# GBEthernet.net
KiCad netlist of a schematic drawn in Altium Designer
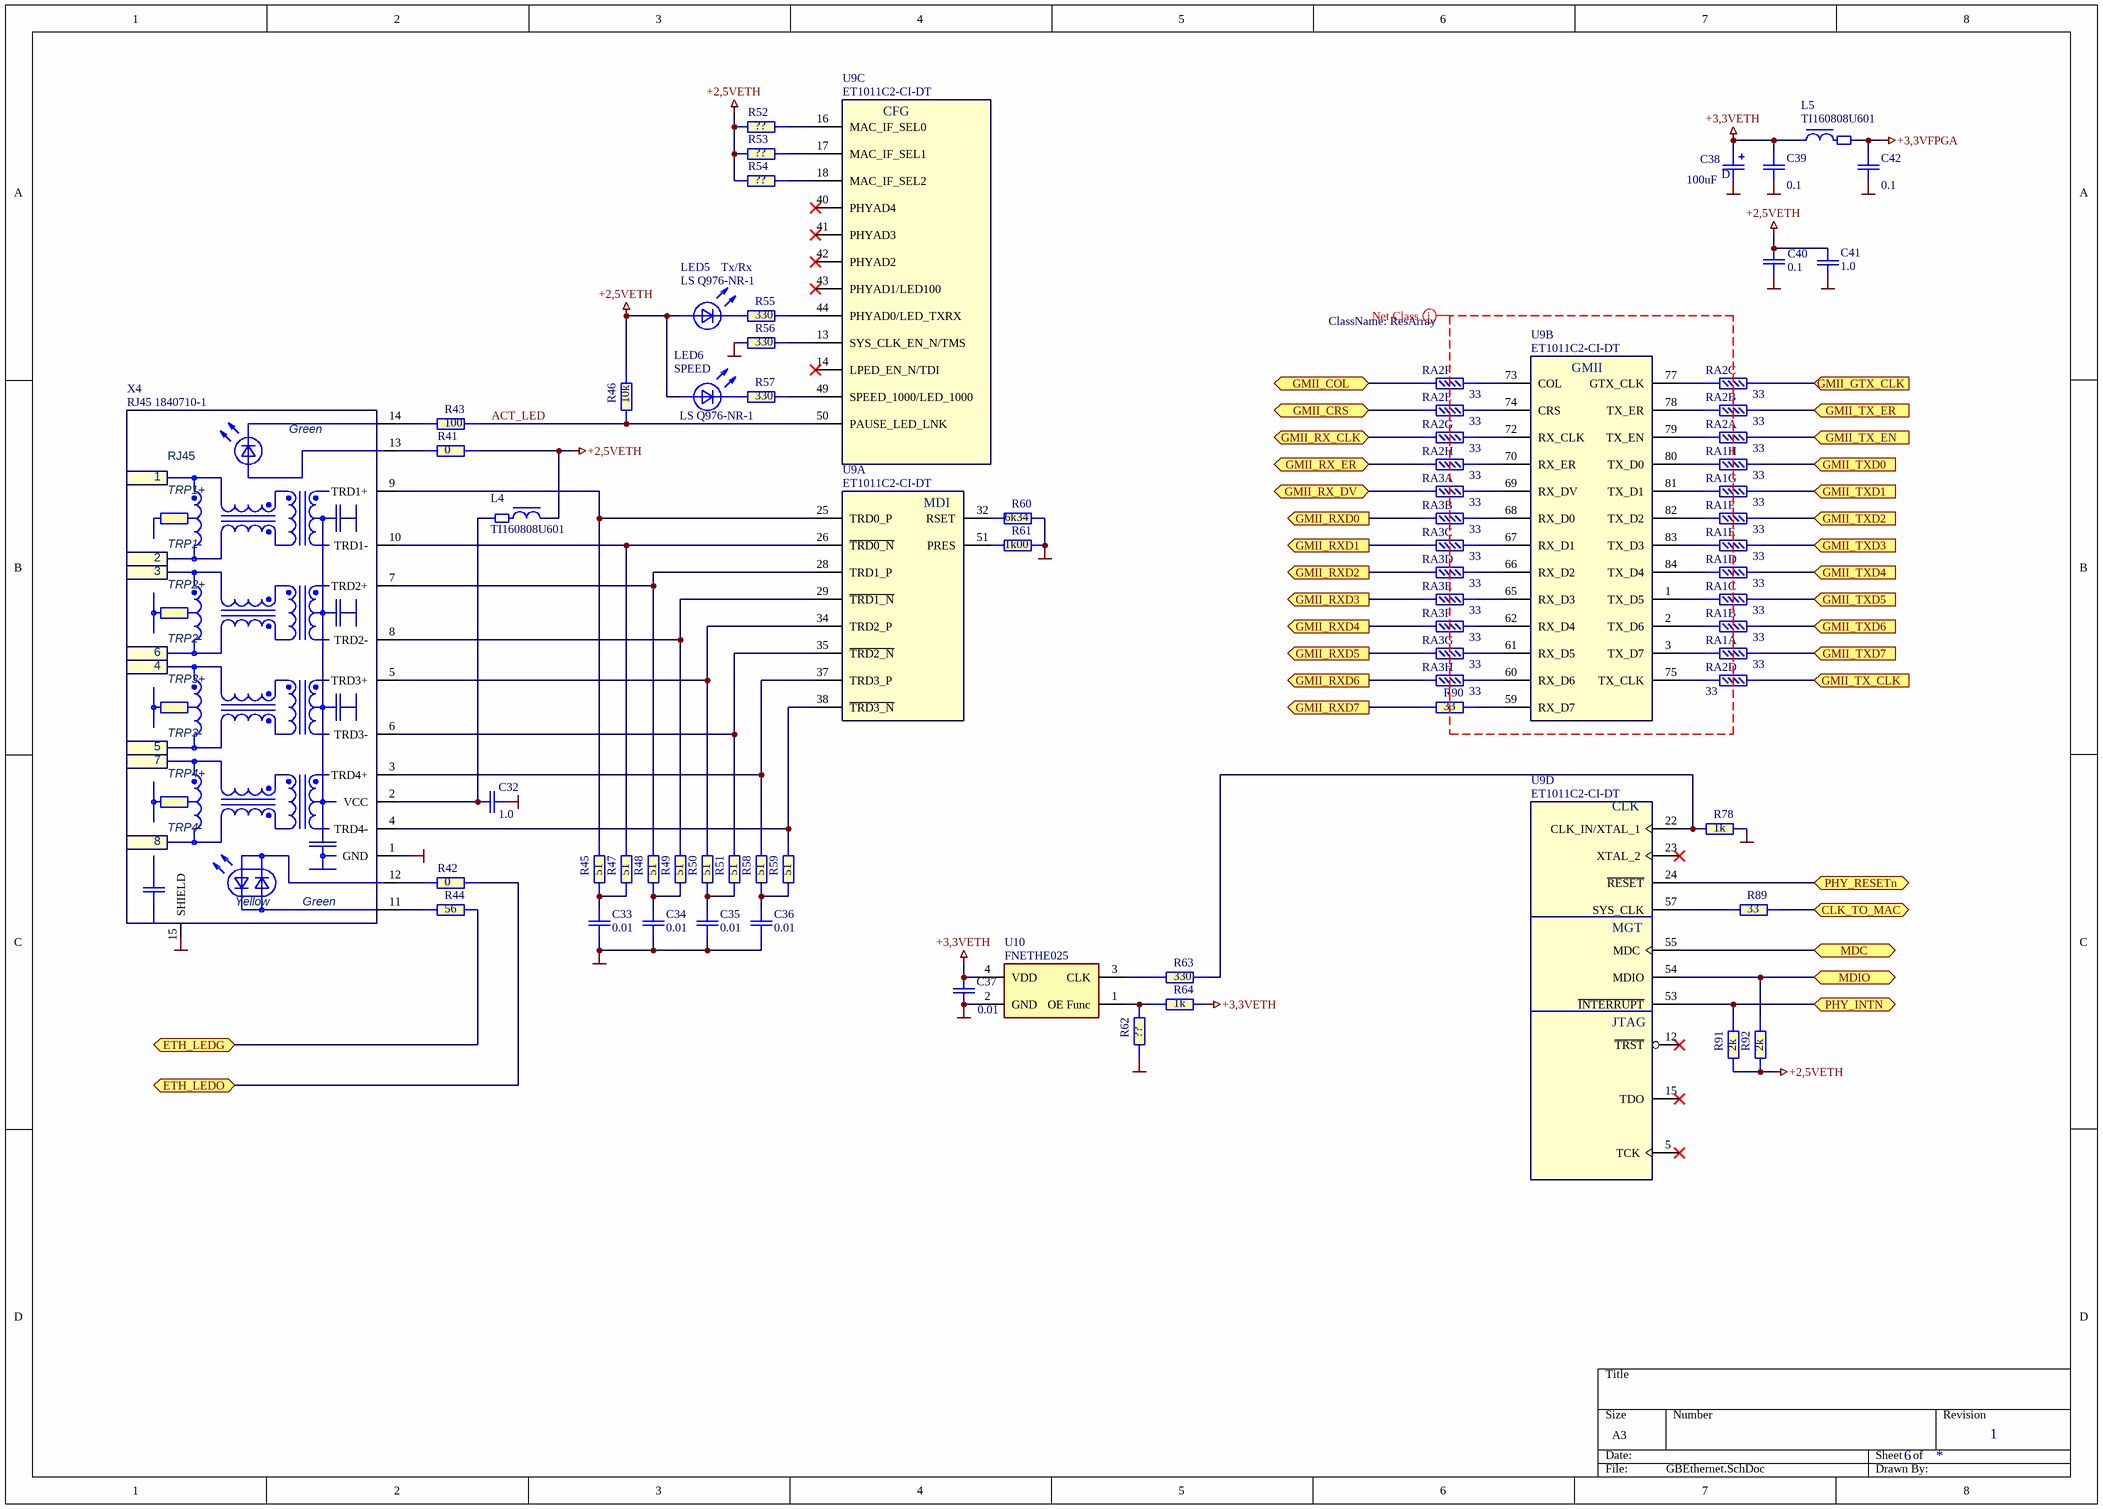
[diagram p0: GBEthernet.SchDoc]

(export (version "E")
  (design (tool "Eeschema 10.0.6"))
  (components
    (comp (ref "C32")
      (value "1.0")
      (footprint "C0603-PHILLIPS")
      (description "Конденсатор")
      (fields (field (name "MANUFACTURER") "MURATA") (field (name "TOLERANCE") "20%"))
      (libsource (lib "Capacitors") (part "C0603"))
    )
    (comp (ref "C33")
      (value "0.01")
      (footprint "C0402-Phillips")
      (description "Конденсатор")
      (fields (field (name "MANUFACTURER") "MURATA") (field (name "TOLERANCE") "20%"))
      (libsource (lib "Capacitors") (part "C0402"))
    )
    (comp (ref "C34")
      (value "0.01")
      (footprint "C0402-Phillips")
      (description "Конденсатор")
      (fields (field (name "MANUFACTURER") "MURATA") (field (name "TOLERANCE") "20%"))
      (libsource (lib "Capacitors") (part "C0402"))
    )
    (comp (ref "C35")
      (value "0.01")
      (footprint "C0402-Phillips")
      (description "Конденсатор")
      (fields (field (name "MANUFACTURER") "MURATA") (field (name "TOLERANCE") "20%"))
      (libsource (lib "Capacitors") (part "C0402"))
    )
    (comp (ref "C36")
      (value "0.01")
      (footprint "C0402-Phillips")
      (description "Конденсатор")
      (fields (field (name "MANUFACTURER") "MURATA") (field (name "TOLERANCE") "20%"))
      (libsource (lib "Capacitors") (part "C0402"))
    )
    (comp (ref "C37")
      (value "0.01")
      (footprint "C0402-Phillips")
      (description "Конденсатор")
      (fields (field (name "MANUFACTURER") "MURATA") (field (name "TOLERANCE") "20%"))
      (libsource (lib "Capacitors") (part "C0402"))
    )
    (comp (ref "C38")
      (value "100uF")
      (footprint "cd7343")
      (description "Конденсатор")
      (fields (field (name "MANUFACTURER") "SPRAGUE"))
      (libsource (lib "Capacitors") (part "CD7343"))
    )
    (comp (ref "C39")
      (value "0.1")
      (footprint "C0402-Phillips")
      (description "Конденсатор")
      (fields (field (name "MANUFACTURER") "MURATA") (field (name "TOLERANCE") "20%"))
      (libsource (lib "Capacitors") (part "C0402"))
    )
    (comp (ref "C40")
      (value "0.1")
      (footprint "C0402-Phillips")
      (description "Конденсатор")
      (fields (field (name "MANUFACTURER") "MURATA") (field (name "TOLERANCE") "20%"))
      (libsource (lib "Capacitors") (part "C0402"))
    )
    (comp (ref "C41")
      (value "1.0")
      (footprint "C0603-PHILLIPS")
      (description "Конденсатор")
      (fields (field (name "MANUFACTURER") "MURATA") (field (name "TOLERANCE") "20%"))
      (libsource (lib "Capacitors") (part "C0603"))
    )
    (comp (ref "C42")
      (value "0.1")
      (footprint "C0402-Phillips")
      (description "Конденсатор")
      (fields (field (name "MANUFACTURER") "MURATA") (field (name "TOLERANCE") "20%"))
      (libsource (lib "Capacitors") (part "C0402"))
    )
    (comp (ref "L4")
      (value "TI160808U601")
      (footprint "Andy:Ti160808-Phillips")
      (description "Дроссель ЭМС")
      (fields (field (name "MANUFACTURER") "MURATA"))
      (libsource (lib "altium-import") (part "root_0_mirrored_TI160808_"))
    )
    (comp (ref "L5")
      (value "TI160808U601")
      (footprint "Andy:Ti160808-Phillips")
      (description "Дроссель ЭМС")
      (fields (field (name "MANUFACTURER") "MURATA"))
      (libsource (lib "altium-import") (part "root_0_TI160808_"))
    )
    (comp (ref "LED5")
      (value "LS Q976-NR-1")
      (footprint "LED-0603y")
      (description "Светодиод")
      (fields (field (name "MANUFACTURER") "OSRAM Opto Semiconductors Inc") (field (name "MISC") "Tx/Rx"))
      (libsource (lib "altium-import") (part "root_1_mirrored_LED0603_"))
    )
    (comp (ref "LED6")
      (value "LS Q976-NR-1")
      (footprint "LED-0603y")
      (description "Светодиод")
      (fields (field (name "MANUFACTURER") "OSRAM Opto Semiconductors Inc") (field (name "MISC") "SPEED"))
      (libsource (lib "altium-import") (part "root_1_mirrored_LED0603_"))
    )
    (comp (ref "R41")
      (value "0")
      (footprint "R0603-PHILLIPS")
      (description "Резистор")
      (fields (field (name "MANUFACTURER") "YAGEO") (field (name "TOLERANCE") "5%"))
      (libsource (lib "altium-import") (part "root_1_R0603_"))
    )
    (comp (ref "R42")
      (value "0")
      (footprint "R0603-PHILLIPS")
      (description "Резистор")
      (fields (field (name "MANUFACTURER") "YAGEO") (field (name "TOLERANCE") "5%"))
      (libsource (lib "altium-import") (part "root_1_R0603_"))
    )
    (comp (ref "R43")
      (value "100")
      (footprint "R0603-PHILLIPS")
      (description "Резистор")
      (fields (field (name "MANUFACTURER") "YAGEO") (field (name "TOLERANCE") "5%"))
      (libsource (lib "altium-import") (part "root_1_R0603_"))
    )
    (comp (ref "R44")
      (value "56")
      (footprint "R0603-PHILLIPS")
      (description "Резистор")
      (fields (field (name "MANUFACTURER") "YAGEO") (field (name "TOLERANCE") "5%"))
      (libsource (lib "altium-import") (part "root_1_R0603_"))
    )
    (comp (ref "R45")
      (value "51")
      (footprint "R0603-PHILLIPS")
      (description "Резистор")
      (fields (field (name "MANUFACTURER") "YAGEO") (field (name "TOLERANCE") "5%"))
      (libsource (lib "altium-import") (part "root_2_R0603_"))
    )
    (comp (ref "R46")
      (value "10k")
      (footprint "R0603-PHILLIPS")
      (description "Резистор")
      (fields (field (name "MANUFACTURER") "YAGEO") (field (name "TOLERANCE") "5%"))
      (libsource (lib "altium-import") (part "root_2_R0603_"))
    )
    (comp (ref "R47")
      (value "51")
      (footprint "R0603-PHILLIPS")
      (description "Резистор")
      (fields (field (name "MANUFACTURER") "YAGEO") (field (name "TOLERANCE") "5%"))
      (libsource (lib "altium-import") (part "root_2_R0603_"))
    )
    (comp (ref "R48")
      (value "51")
      (footprint "R0603-PHILLIPS")
      (description "Резистор")
      (fields (field (name "MANUFACTURER") "YAGEO") (field (name "TOLERANCE") "5%"))
      (libsource (lib "altium-import") (part "root_2_R0603_"))
    )
    (comp (ref "R49")
      (value "51")
      (footprint "R0603-PHILLIPS")
      (description "Резистор")
      (fields (field (name "MANUFACTURER") "YAGEO") (field (name "TOLERANCE") "5%"))
      (libsource (lib "altium-import") (part "root_2_R0603_"))
    )
    (comp (ref "R50")
      (value "51")
      (footprint "R0603-PHILLIPS")
      (description "Резистор")
      (fields (field (name "MANUFACTURER") "YAGEO") (field (name "TOLERANCE") "5%"))
      (libsource (lib "altium-import") (part "root_2_R0603_"))
    )
    (comp (ref "R51")
      (value "51")
      (footprint "R0603-PHILLIPS")
      (description "Резистор")
      (fields (field (name "MANUFACTURER") "YAGEO") (field (name "TOLERANCE") "5%"))
      (libsource (lib "altium-import") (part "root_2_R0603_"))
    )
    (comp (ref "R52")
      (value "??")
      (footprint "R0603-PHILLIPS")
      (description "Резистор")
      (fields (field (name "MANUFACTURER") "YAGEO") (field (name "TOLERANCE") "5%"))
      (libsource (lib "altium-import") (part "root_1_R0603_"))
    )
    (comp (ref "R53")
      (value "??")
      (footprint "R0603-PHILLIPS")
      (description "Резистор")
      (fields (field (name "MANUFACTURER") "YAGEO") (field (name "TOLERANCE") "5%"))
      (libsource (lib "altium-import") (part "root_1_R0603_"))
    )
    (comp (ref "R54")
      (value "??")
      (footprint "R0603-PHILLIPS")
      (description "Резистор")
      (fields (field (name "MANUFACTURER") "YAGEO") (field (name "TOLERANCE") "5%"))
      (libsource (lib "altium-import") (part "root_1_R0603_"))
    )
    (comp (ref "R55")
      (value "330")
      (footprint "R0603-PHILLIPS")
      (description "Резистор")
      (fields (field (name "MANUFACTURER") "YAGEO") (field (name "TOLERANCE") "5%"))
      (libsource (lib "altium-import") (part "root_1_R0603_"))
    )
    (comp (ref "R56")
      (value "330")
      (footprint "R0603-PHILLIPS")
      (description "Резистор")
      (fields (field (name "MANUFACTURER") "YAGEO") (field (name "TOLERANCE") "5%"))
      (libsource (lib "altium-import") (part "root_1_R0603_"))
    )
    (comp (ref "R57")
      (value "330")
      (footprint "R0603-PHILLIPS")
      (description "Резистор")
      (fields (field (name "MANUFACTURER") "YAGEO") (field (name "TOLERANCE") "5%"))
      (libsource (lib "altium-import") (part "root_1_R0603_"))
    )
    (comp (ref "R58")
      (value "51")
      (footprint "R0603-PHILLIPS")
      (description "Резистор")
      (fields (field (name "MANUFACTURER") "YAGEO") (field (name "TOLERANCE") "5%"))
      (libsource (lib "altium-import") (part "root_2_R0603_"))
    )
    (comp (ref "R59")
      (value "51")
      (footprint "R0603-PHILLIPS")
      (description "Резистор")
      (fields (field (name "MANUFACTURER") "YAGEO") (field (name "TOLERANCE") "5%"))
      (libsource (lib "altium-import") (part "root_2_R0603_"))
    )
    (comp (ref "R60")
      (value "6k34")
      (footprint "R0603-PHILLIPS")
      (description "Резистор")
      (fields (field (name "MANUFACTURER") "YAGEO") (field (name "TOLERANCE") "1%"))
      (libsource (lib "altium-import") (part "root_1_R0603_"))
    )
    (comp (ref "R61")
      (value "1k00")
      (footprint "R0603-PHILLIPS")
      (description "Резистор")
      (fields (field (name "MANUFACTURER") "YAGEO") (field (name "TOLERANCE") "1%"))
      (libsource (lib "altium-import") (part "root_1_R0603_"))
    )
    (comp (ref "R62")
      (value "??")
      (footprint "R0603-PHILLIPS")
      (description "Резистор")
      (fields (field (name "MANUFACTURER") "YAGEO") (field (name "TOLERANCE") "5%"))
      (libsource (lib "altium-import") (part "root_2_R0603_"))
    )
    (comp (ref "R63")
      (value "330")
      (footprint "R0603-PHILLIPS")
      (description "Резистор")
      (fields (field (name "MANUFACTURER") "YAGEO") (field (name "TOLERANCE") "5%"))
      (libsource (lib "altium-import") (part "root_1_R0603_"))
    )
    (comp (ref "R64")
      (value "1k")
      (footprint "R0603-PHILLIPS")
      (description "Резистор")
      (fields (field (name "MANUFACTURER") "YAGEO") (field (name "TOLERANCE") "5%"))
      (libsource (lib "altium-import") (part "root_1_R0603_"))
    )
    (comp (ref "R78")
      (value "1k")
      (footprint "R0603-PHILLIPS")
      (description "Резистор")
      (fields (field (name "MANUFACTURER") "YAGEO") (field (name "TOLERANCE") "5%"))
      (libsource (lib "altium-import") (part "root_1_R0603_"))
    )
    (comp (ref "R89")
      (value "33")
      (footprint "R0603-PHILLIPS")
      (description "Резистор")
      (fields (field (name "MANUFACTURER") "YAGEO") (field (name "TOLERANCE") "5%"))
      (libsource (lib "altium-import") (part "root_1_R0603_"))
    )
    (comp (ref "R90")
      (value "33")
      (footprint "R0603-PHILLIPS")
      (description "Резистор")
      (fields (field (name "MANUFACTURER") "YAGEO") (field (name "TOLERANCE") "5%"))
      (libsource (lib "altium-import") (part "root_1_R0603_"))
    )
    (comp (ref "R91")
      (value "2k")
      (footprint "R0603-PHILLIPS")
      (description "Резистор")
      (fields (field (name "MANUFACTURER") "YAGEO") (field (name "TOLERANCE") "5%"))
      (libsource (lib "altium-import") (part "root_2_R0603_"))
    )
    (comp (ref "R92")
      (value "2k")
      (footprint "R0603-PHILLIPS")
      (description "Резистор")
      (fields (field (name "MANUFACTURER") "YAGEO") (field (name "TOLERANCE") "5%"))
      (libsource (lib "altium-import") (part "root_2_R0603_"))
    )
    (comp (ref "RA1")
      (value "33")
      (footprint "YC248")
      (description "Резисторна  сборка")
      (fields (field (name "TOLERANCE") "5%") (field (name "MANUFACTURER") "Yageo"))
      (libsource (lib "") (part "YC248_1"))
    )
    (comp (ref "RA2")
      (value "33")
      (footprint "YC248")
      (description "Резисторна  сборка")
      (fields (field (name "TOLERANCE") "5%") (field (name "MANUFACTURER") "Yageo"))
      (libsource (lib "Resistors") (part "YC248"))
    )
    (comp (ref "RA3")
      (value "33")
      (footprint "YC248")
      (description "Резисторна  сборка")
      (fields (field (name "TOLERANCE") "5%") (field (name "MANUFACTURER") "Yageo"))
      (libsource (lib "Resistors") (part "YC248"))
    )
    (comp (ref "U9")
      (value "ET1011C2-CI-DT")
      (footprint "QFN-84(10x10/0/4mm)with_pad")
      (description "Микросхема")
      (fields (field (name "MANUFACTURER") "LSI"))
      (libsource (lib "altium-import") (part "root_0_ET1011C2-CI-DT_"))
    )
    (comp (ref "U10")
      (value "FNETHE025")
      (footprint "7x5mm")
      (description "Генератор")
      (fields (field (name "MANUFACTURER") "Saronix-eCera"))
      (libsource (lib "altium-import") (part "root_0_mirrored_FNETHE025_"))
    )
    (comp (ref "X4")
      (value "RJ45 1840710-1")
      (footprint "RJ45 1840710-x")
      (description "Модуль разъёма RJ45")
      (fields (field (name "MANUFACTURER") "Tyco Electronics AMP"))
      (libsource (lib "Andy") (part "RJ45 1840710-5"))
    )
  )
  (nets
    (net (code "1") (name "+2,5VETH") (class "Default")
      (node (ref "C40") (pin "1") (pinfunction "1_1") (pintype "passive"))
      (node (ref "C41") (pin "2") (pinfunction "2_2") (pintype "passive"))
      (node (ref "L4") (pin "1") (pinfunction "1_1") (pintype "passive"))
      (node (ref "LED5") (pin "2") (pinfunction "A_2") (pintype "passive"))
      (node (ref "LED6") (pin "2") (pinfunction "A_2") (pintype "passive"))
      (node (ref "R41") (pin "2") (pinfunction "2_2") (pintype "passive"))
      (node (ref "R46") (pin "2") (pinfunction "2_2") (pintype "passive"))
      (node (ref "R52") (pin "1") (pinfunction "1_1") (pintype "passive"))
      (node (ref "R53") (pin "1") (pinfunction "1_1") (pintype "passive"))
      (node (ref "R54") (pin "1") (pinfunction "1_1") (pintype "passive"))
      (node (ref "R91") (pin "1") (pinfunction "1_1") (pintype "passive"))
      (node (ref "R92") (pin "1") (pinfunction "1_1") (pintype "passive"))
    )
    (net (code "2") (name "+3,3VETH") (class "Default")
      (node (ref "C37") (pin "1") (pinfunction "1_1") (pintype "passive"))
      (node (ref "C38") (pin "1") (pinfunction "+_1") (pintype "passive"))
      (node (ref "C39") (pin "1") (pinfunction "1_1") (pintype "passive"))
      (node (ref "L5") (pin "1") (pinfunction "1_1") (pintype "passive"))
      (node (ref "R64") (pin "2") (pinfunction "2_2") (pintype "passive"))
      (node (ref "U10") (pin "4") (pinfunction "VDD_4") (pintype "passive"))
    )
    (net (code "3") (name "+3,3VFPGA") (class "Default")
      (node (ref "C42") (pin "1") (pinfunction "1_1") (pintype "passive"))
      (node (ref "L5") (pin "2") (pinfunction "2_2") (pintype "passive"))
    )
    (net (code "4") (name "/ACT_LED") (class "Default")
      (node (ref "R43") (pin "2") (pinfunction "2_2") (pintype "passive"))
      (node (ref "R46") (pin "1") (pinfunction "1_1") (pintype "passive"))
      (node (ref "U9") (pin "50") (pinfunction "PAUSE_LED_LNK_50") (pintype "passive"))
    )
    (net (code "5") (name "/CLK_TO_MAC") (class "Default")
      (node (ref "R89") (pin "2") (pinfunction "2_2") (pintype "passive"))
    )
    (net (code "6") (name "/ETH_LEDG") (class "Default")
      (node (ref "R44") (pin "2") (pinfunction "2_2") (pintype "passive"))
    )
    (net (code "7") (name "/ETH_LEDO") (class "Default")
      (node (ref "R42") (pin "2") (pinfunction "2_2") (pintype "passive"))
    )
    (net (code "8") (name "/GMII_COL") (class "Default")
      (node (ref "RA2") (pin "11") (pinfunction "2_11") (pintype "passive"))
    )
    (net (code "9") (name "/GMII_CRS") (class "Default")
      (node (ref "RA2") (pin "12") (pinfunction "2_12") (pintype "passive"))
    )
    (net (code "10") (name "/GMII_GTX_CLK") (class "Default")
      (node (ref "RA2") (pin "14") (pinfunction "2_14") (pintype "passive"))
    )
    (net (code "11") (name "/GMII_RXD0") (class "Default")
      (node (ref "RA3") (pin "15") (pinfunction "2_15") (pintype "passive"))
    )
    (net (code "12") (name "/GMII_RXD1") (class "Default")
      (node (ref "RA3") (pin "14") (pinfunction "2_14") (pintype "passive"))
    )
    (net (code "13") (name "/GMII_RXD2") (class "Default")
      (node (ref "RA3") (pin "13") (pinfunction "2_13") (pintype "passive"))
    )
    (net (code "14") (name "/GMII_RXD3") (class "Default")
      (node (ref "RA3") (pin "12") (pinfunction "2_12") (pintype "passive"))
    )
    (net (code "15") (name "/GMII_RXD4") (class "Default")
      (node (ref "RA3") (pin "11") (pinfunction "2_11") (pintype "passive"))
    )
    (net (code "16") (name "/GMII_RXD5") (class "Default")
      (node (ref "RA3") (pin "10") (pinfunction "2_10") (pintype "passive"))
    )
    (net (code "17") (name "/GMII_RXD6") (class "Default")
      (node (ref "RA3") (pin "9") (pinfunction "2_9") (pintype "passive"))
    )
    (net (code "18") (name "/GMII_RXD7") (class "Default")
      (node (ref "R90") (pin "1") (pinfunction "1_1") (pintype "passive"))
    )
    (net (code "19") (name "/GMII_RX_CLK") (class "Default")
      (node (ref "RA2") (pin "10") (pinfunction "2_10") (pintype "passive"))
    )
    (net (code "20") (name "/GMII_RX_DV") (class "Default")
      (node (ref "RA3") (pin "16") (pinfunction "2_16") (pintype "passive"))
    )
    (net (code "21") (name "/GMII_RX_ER") (class "Default")
      (node (ref "RA2") (pin "9") (pinfunction "2_9") (pintype "passive"))
    )
    (net (code "22") (name "/GMII_TXD0") (class "Default")
      (node (ref "RA1") (pin "9") (pinfunction "2_9") (pintype "passive"))
    )
    (net (code "23") (name "/GMII_TXD1") (class "Default")
      (node (ref "RA1") (pin "10") (pinfunction "2_10") (pintype "passive"))
    )
    (net (code "24") (name "/GMII_TXD2") (class "Default")
      (node (ref "RA1") (pin "11") (pinfunction "2_11") (pintype "passive"))
    )
    (net (code "25") (name "/GMII_TXD3") (class "Default")
      (node (ref "RA1") (pin "12") (pinfunction "2_12") (pintype "passive"))
    )
    (net (code "26") (name "/GMII_TXD4") (class "Default")
      (node (ref "RA1") (pin "13") (pinfunction "2_13") (pintype "passive"))
    )
    (net (code "27") (name "/GMII_TXD5") (class "Default")
      (node (ref "RA1") (pin "14") (pinfunction "2_14") (pintype "passive"))
    )
    (net (code "28") (name "/GMII_TXD6") (class "Default")
      (node (ref "RA1") (pin "15") (pinfunction "2_15") (pintype "passive"))
    )
    (net (code "29") (name "/GMII_TXD7") (class "Default")
      (node (ref "RA1") (pin "16") (pinfunction "2_16") (pintype "passive"))
    )
    (net (code "30") (name "/GMII_TX_CLK") (class "Default")
      (node (ref "RA2") (pin "13") (pinfunction "2_13") (pintype "passive"))
    )
    (net (code "31") (name "/GMII_TX_EN") (class "Default")
      (node (ref "RA2") (pin "16") (pinfunction "2_16") (pintype "passive"))
    )
    (net (code "32") (name "/GMII_TX_ER") (class "Default")
      (node (ref "RA2") (pin "15") (pinfunction "2_15") (pintype "passive"))
    )
    (net (code "33") (name "/MDC") (class "Default")
      (node (ref "U9") (pin "55") (pinfunction "MDC_55") (pintype "passive"))
    )
    (net (code "34") (name "/MDIO") (class "Default")
      (node (ref "R92") (pin "2") (pinfunction "2_2") (pintype "passive"))
      (node (ref "U9") (pin "54") (pinfunction "MDIO_54") (pintype "passive"))
    )
    (net (code "35") (name "/PHY_INTN") (class "Default")
      (node (ref "R91") (pin "2") (pinfunction "2_2") (pintype "passive"))
      (node (ref "U9") (pin "53") (pinfunction "~{INTERRUPT}_53") (pintype "passive"))
    )
    (net (code "36") (name "/PHY_RESETn") (class "Default")
      (node (ref "U9") (pin "24") (pinfunction "~{RESET}_24") (pintype "passive"))
    )
    (net (code "37") (name "GND") (class "Default")
      (node (ref "C32") (pin "1") (pinfunction "1_1") (pintype "passive"))
      (node (ref "C33") (pin "2") (pinfunction "2_2") (pintype "passive"))
      (node (ref "C34") (pin "2") (pinfunction "2_2") (pintype "passive"))
      (node (ref "C35") (pin "2") (pinfunction "2_2") (pintype "passive"))
      (node (ref "C36") (pin "2") (pinfunction "2_2") (pintype "passive"))
      (node (ref "C37") (pin "2") (pinfunction "2_2") (pintype "passive"))
      (node (ref "C38") (pin "2") (pinfunction "-_2") (pintype "passive"))
      (node (ref "C39") (pin "2") (pinfunction "2_2") (pintype "passive"))
      (node (ref "C40") (pin "2") (pinfunction "2_2") (pintype "passive"))
      (node (ref "C41") (pin "1") (pinfunction "1_1") (pintype "passive"))
      (node (ref "C42") (pin "2") (pinfunction "2_2") (pintype "passive"))
      (node (ref "R56") (pin "1") (pinfunction "1_1") (pintype "passive"))
      (node (ref "R60") (pin "2") (pinfunction "2_2") (pintype "passive"))
      (node (ref "R61") (pin "2") (pinfunction "2_2") (pintype "passive"))
      (node (ref "R62") (pin "1") (pinfunction "1_1") (pintype "passive"))
      (node (ref "R78") (pin "2") (pinfunction "2_2") (pintype "passive"))
      (node (ref "U10") (pin "2") (pinfunction "GND_2") (pintype "passive"))
      (node (ref "X4") (pin "1") (pinfunction "GND_1") (pintype "passive"))
      (node (ref "X4") (pin "15") (pinfunction "SHIELD_15") (pintype "passive"))
    )
    (net (code "38") (name "Net-(C33-Pad1)") (class "Default")
      (node (ref "C33") (pin "1") (pinfunction "1_1") (pintype "passive"))
      (node (ref "R45") (pin "1") (pinfunction "1_1") (pintype "passive"))
      (node (ref "R47") (pin "1") (pinfunction "1_1") (pintype "passive"))
    )
    (net (code "39") (name "Net-(C34-Pad1)") (class "Default")
      (node (ref "C34") (pin "1") (pinfunction "1_1") (pintype "passive"))
      (node (ref "R48") (pin "1") (pinfunction "1_1") (pintype "passive"))
      (node (ref "R49") (pin "1") (pinfunction "1_1") (pintype "passive"))
    )
    (net (code "40") (name "Net-(C35-Pad1)") (class "Default")
      (node (ref "C35") (pin "1") (pinfunction "1_1") (pintype "passive"))
      (node (ref "R50") (pin "1") (pinfunction "1_1") (pintype "passive"))
      (node (ref "R51") (pin "1") (pinfunction "1_1") (pintype "passive"))
    )
    (net (code "41") (name "Net-(C36-Pad1)") (class "Default")
      (node (ref "C36") (pin "1") (pinfunction "1_1") (pintype "passive"))
      (node (ref "R58") (pin "1") (pinfunction "1_1") (pintype "passive"))
      (node (ref "R59") (pin "1") (pinfunction "1_1") (pintype "passive"))
    )
    (net (code "42") (name "Net-(LED5-K)") (class "Default")
      (node (ref "LED5") (pin "1") (pinfunction "K_1") (pintype "passive"))
      (node (ref "R55") (pin "1") (pinfunction "1_1") (pintype "passive"))
    )
    (net (code "43") (name "Net-(LED6-K)") (class "Default")
      (node (ref "LED6") (pin "1") (pinfunction "K_1") (pintype "passive"))
      (node (ref "R57") (pin "1") (pinfunction "1_1") (pintype "passive"))
    )
    (net (code "44") (name "Net-(RA1B-1)") (class "Default")
      (node (ref "RA1") (pin "2") (pinfunction "1_2") (pintype "passive"))
      (node (ref "U9") (pin "2") (pinfunction "TX_D6_2") (pintype "passive"))
    )
    (net (code "45") (name "Net-(RA1C-1)") (class "Default")
      (node (ref "RA1") (pin "3") (pinfunction "1_3") (pintype "passive"))
      (node (ref "U9") (pin "1") (pinfunction "TX_D5_1") (pintype "passive"))
    )
    (net (code "46") (name "Net-(RA1D-1)") (class "Default")
      (node (ref "RA1") (pin "4") (pinfunction "1_4") (pintype "passive"))
      (node (ref "U9") (pin "84") (pinfunction "TX_D4_84") (pintype "passive"))
    )
    (net (code "47") (name "Net-(RA1E-1)") (class "Default")
      (node (ref "RA1") (pin "5") (pinfunction "1_5") (pintype "passive"))
      (node (ref "U9") (pin "83") (pinfunction "TX_D3_83") (pintype "passive"))
    )
    (net (code "48") (name "Net-(RA1F-1)") (class "Default")
      (node (ref "RA1") (pin "6") (pinfunction "1_6") (pintype "passive"))
      (node (ref "U9") (pin "82") (pinfunction "TX_D2_82") (pintype "passive"))
    )
    (net (code "49") (name "Net-(RA1G-1)") (class "Default")
      (node (ref "RA1") (pin "7") (pinfunction "1_7") (pintype "passive"))
      (node (ref "U9") (pin "81") (pinfunction "TX_D1_81") (pintype "passive"))
    )
    (net (code "50") (name "Net-(RA1H-1)") (class "Default")
      (node (ref "RA1") (pin "8") (pinfunction "1_8") (pintype "passive"))
      (node (ref "U9") (pin "80") (pinfunction "TX_D0_80") (pintype "passive"))
    )
    (net (code "51") (name "Net-(RA2B-1)") (class "Default")
      (node (ref "RA2") (pin "2") (pinfunction "1_2") (pintype "passive"))
      (node (ref "U9") (pin "78") (pinfunction "TX_ER_78") (pintype "passive"))
    )
    (net (code "52") (name "Net-(RA2C-1)") (class "Default")
      (node (ref "RA2") (pin "3") (pinfunction "1_3") (pintype "passive"))
      (node (ref "U9") (pin "77") (pinfunction "GTX_CLK_77") (pintype "passive"))
    )
    (net (code "53") (name "Net-(RA2D-1)") (class "Default")
      (node (ref "RA2") (pin "4") (pinfunction "1_4") (pintype "passive"))
      (node (ref "U9") (pin "75") (pinfunction "TX_CLK_75") (pintype "passive"))
    )
    (net (code "54") (name "Net-(RA2E-1)") (class "Default")
      (node (ref "RA2") (pin "5") (pinfunction "1_5") (pintype "passive"))
      (node (ref "U9") (pin "74") (pinfunction "CRS_74") (pintype "passive"))
    )
    (net (code "55") (name "Net-(RA2F-1)") (class "Default")
      (node (ref "RA2") (pin "6") (pinfunction "1_6") (pintype "passive"))
      (node (ref "U9") (pin "73") (pinfunction "COL_73") (pintype "passive"))
    )
    (net (code "56") (name "Net-(RA2G-1)") (class "Default")
      (node (ref "RA2") (pin "7") (pinfunction "1_7") (pintype "passive"))
      (node (ref "U9") (pin "72") (pinfunction "RX_CLK_72") (pintype "passive"))
    )
    (net (code "57") (name "Net-(RA2H-1)") (class "Default")
      (node (ref "RA2") (pin "8") (pinfunction "1_8") (pintype "passive"))
      (node (ref "U9") (pin "70") (pinfunction "RX_ER_70") (pintype "passive"))
    )
    (net (code "58") (name "Net-(RA3B-1)") (class "Default")
      (node (ref "RA3") (pin "2") (pinfunction "1_2") (pintype "passive"))
      (node (ref "U9") (pin "68") (pinfunction "RX_D0_68") (pintype "passive"))
    )
    (net (code "59") (name "Net-(RA3C-1)") (class "Default")
      (node (ref "RA3") (pin "3") (pinfunction "1_3") (pintype "passive"))
      (node (ref "U9") (pin "67") (pinfunction "RX_D1_67") (pintype "passive"))
    )
    (net (code "60") (name "Net-(RA3D-1)") (class "Default")
      (node (ref "RA3") (pin "4") (pinfunction "1_4") (pintype "passive"))
      (node (ref "U9") (pin "66") (pinfunction "RX_D2_66") (pintype "passive"))
    )
    (net (code "61") (name "Net-(RA3E-1)") (class "Default")
      (node (ref "RA3") (pin "5") (pinfunction "1_5") (pintype "passive"))
      (node (ref "U9") (pin "65") (pinfunction "RX_D3_65") (pintype "passive"))
    )
    (net (code "62") (name "Net-(RA3F-1)") (class "Default")
      (node (ref "RA3") (pin "6") (pinfunction "1_6") (pintype "passive"))
      (node (ref "U9") (pin "62") (pinfunction "RX_D4_62") (pintype "passive"))
    )
    (net (code "63") (name "Net-(RA3G-1)") (class "Default")
      (node (ref "RA3") (pin "7") (pinfunction "1_7") (pintype "passive"))
      (node (ref "U9") (pin "61") (pinfunction "RX_D5_61") (pintype "passive"))
    )
    (net (code "64") (name "Net-(RA3H-1)") (class "Default")
      (node (ref "RA3") (pin "8") (pinfunction "1_8") (pintype "passive"))
      (node (ref "U9") (pin "60") (pinfunction "RX_D6_60") (pintype "passive"))
    )
    (net (code "65") (name "Net-(U9A-PRES)") (class "Default")
      (node (ref "R61") (pin "1") (pinfunction "1_1") (pintype "passive"))
      (node (ref "U9") (pin "51") (pinfunction "PRES_51") (pintype "passive"))
    )
    (net (code "66") (name "Net-(U9A-RSET)") (class "Default")
      (node (ref "R60") (pin "1") (pinfunction "1_1") (pintype "passive"))
      (node (ref "U9") (pin "32") (pinfunction "RSET_32") (pintype "passive"))
    )
    (net (code "67") (name "Net-(U9A-TRD0_P)") (class "Default")
      (node (ref "R45") (pin "2") (pinfunction "2_2") (pintype "passive"))
      (node (ref "U9") (pin "25") (pinfunction "TRD0_P_25") (pintype "passive"))
      (node (ref "X4") (pin "9") (pinfunction "TRD1+_9") (pintype "passive"))
    )
    (net (code "68") (name "Net-(U9A-TRD1_P)") (class "Default")
      (node (ref "R48") (pin "2") (pinfunction "2_2") (pintype "passive"))
      (node (ref "U9") (pin "28") (pinfunction "TRD1_P_28") (pintype "passive"))
      (node (ref "X4") (pin "7") (pinfunction "TRD2+_7") (pintype "passive"))
    )
    (net (code "69") (name "Net-(U9A-TRD2_P)") (class "Default")
      (node (ref "R50") (pin "2") (pinfunction "2_2") (pintype "passive"))
      (node (ref "U9") (pin "34") (pinfunction "TRD2_P_34") (pintype "passive"))
      (node (ref "X4") (pin "5") (pinfunction "TRD3+_5") (pintype "passive"))
    )
    (net (code "70") (name "Net-(U9A-TRD3_P)") (class "Default")
      (node (ref "R58") (pin "2") (pinfunction "2_2") (pintype "passive"))
      (node (ref "U9") (pin "37") (pinfunction "TRD3_P_37") (pintype "passive"))
      (node (ref "X4") (pin "3") (pinfunction "TRD4+_3") (pintype "passive"))
    )
    (net (code "71") (name "Net-(U9A-~{TRD0_N})") (class "Default")
      (node (ref "R47") (pin "2") (pinfunction "2_2") (pintype "passive"))
      (node (ref "U9") (pin "26") (pinfunction "~{TRD0_N}_26") (pintype "passive"))
      (node (ref "X4") (pin "10") (pinfunction "TRD1-_10") (pintype "passive"))
    )
    (net (code "72") (name "Net-(U9A-~{TRD1_N})") (class "Default")
      (node (ref "R49") (pin "2") (pinfunction "2_2") (pintype "passive"))
      (node (ref "U9") (pin "29") (pinfunction "~{TRD1_N}_29") (pintype "passive"))
      (node (ref "X4") (pin "8") (pinfunction "TRD2-_8") (pintype "passive"))
    )
    (net (code "73") (name "Net-(U9A-~{TRD2_N})") (class "Default")
      (node (ref "R51") (pin "2") (pinfunction "2_2") (pintype "passive"))
      (node (ref "U9") (pin "35") (pinfunction "~{TRD2_N}_35") (pintype "passive"))
      (node (ref "X4") (pin "6") (pinfunction "TRD3-_6") (pintype "passive"))
    )
    (net (code "74") (name "Net-(U9A-~{TRD3_N})") (class "Default")
      (node (ref "R59") (pin "2") (pinfunction "2_2") (pintype "passive"))
      (node (ref "U9") (pin "38") (pinfunction "~{TRD3_N}_38") (pintype "passive"))
      (node (ref "X4") (pin "4") (pinfunction "TRD4-_4") (pintype "passive"))
    )
    (net (code "75") (name "Net-(U9B-RX_D7)") (class "Default")
      (node (ref "R90") (pin "2") (pinfunction "2_2") (pintype "passive"))
      (node (ref "U9") (pin "59") (pinfunction "RX_D7_59") (pintype "passive"))
    )
    (net (code "76") (name "Net-(U9B-RX_DV)") (class "Default")
      (node (ref "RA3") (pin "1") (pinfunction "1_1") (pintype "passive"))
      (node (ref "U9") (pin "69") (pinfunction "RX_DV_69") (pintype "passive"))
    )
    (net (code "77") (name "Net-(U9B-TX_D7)") (class "Default")
      (node (ref "RA1") (pin "1") (pinfunction "1_1") (pintype "passive"))
      (node (ref "U9") (pin "3") (pinfunction "TX_D7_3") (pintype "passive"))
    )
    (net (code "78") (name "Net-(U9B-TX_EN)") (class "Default")
      (node (ref "RA2") (pin "1") (pinfunction "1_1") (pintype "passive"))
      (node (ref "U9") (pin "79") (pinfunction "TX_EN_79") (pintype "passive"))
    )
    (net (code "79") (name "Net-(U9C-MAC_IF_SEL0)") (class "Default")
      (node (ref "R52") (pin "2") (pinfunction "2_2") (pintype "passive"))
      (node (ref "U9") (pin "16") (pinfunction "MAC_IF_SEL0_16") (pintype "passive"))
    )
    (net (code "80") (name "Net-(U9C-MAC_IF_SEL1)") (class "Default")
      (node (ref "R53") (pin "2") (pinfunction "2_2") (pintype "passive"))
      (node (ref "U9") (pin "17") (pinfunction "MAC_IF_SEL1_17") (pintype "passive"))
    )
    (net (code "81") (name "Net-(U9C-MAC_IF_SEL2)") (class "Default")
      (node (ref "R54") (pin "2") (pinfunction "2_2") (pintype "passive"))
      (node (ref "U9") (pin "18") (pinfunction "MAC_IF_SEL2_18") (pintype "passive"))
    )
    (net (code "82") (name "Net-(U9C-PHYAD0{slash}LED_TXRX)") (class "Default")
      (node (ref "R55") (pin "2") (pinfunction "2_2") (pintype "passive"))
      (node (ref "U9") (pin "44") (pinfunction "PHYAD0/LED_TXRX_44") (pintype "passive"))
    )
    (net (code "83") (name "Net-(U9C-SPEED_1000{slash}LED_1000)") (class "Default")
      (node (ref "R57") (pin "2") (pinfunction "2_2") (pintype "passive"))
      (node (ref "U9") (pin "49") (pinfunction "SPEED_1000/LED_1000_49") (pintype "passive"))
    )
    (net (code "84") (name "Net-(U9C-SYS_CLK_EN_N{slash}TMS)") (class "Default")
      (node (ref "R56") (pin "2") (pinfunction "2_2") (pintype "passive"))
      (node (ref "U9") (pin "13") (pinfunction "SYS_CLK_EN_N/TMS_13") (pintype "passive"))
    )
    (net (code "85") (name "Net-(U9D-CLK_IN{slash}XTAL_1)") (class "Default")
      (node (ref "R63") (pin "2") (pinfunction "2_2") (pintype "passive"))
      (node (ref "R78") (pin "1") (pinfunction "1_1") (pintype "passive"))
      (node (ref "U9") (pin "22") (pinfunction "CLK_IN/XTAL_1_22") (pintype "passive"))
    )
    (net (code "86") (name "Net-(U9D-SYS_CLK)") (class "Default")
      (node (ref "R89") (pin "1") (pinfunction "1_1") (pintype "passive"))
      (node (ref "U9") (pin "57") (pinfunction "SYS_CLK_57") (pintype "passive"))
    )
    (net (code "87") (name "Net-(U10-CLK)") (class "Default")
      (node (ref "R63") (pin "1") (pinfunction "1_1") (pintype "passive"))
      (node (ref "U10") (pin "3") (pinfunction "CLK_3") (pintype "passive"))
    )
    (net (code "88") (name "Net-(U10-OE_Func)") (class "Default")
      (node (ref "R62") (pin "2") (pinfunction "2_2") (pintype "passive"))
      (node (ref "R64") (pin "1") (pinfunction "1_1") (pintype "passive"))
      (node (ref "U10") (pin "1") (pinfunction "OE_Func_1") (pintype "passive"))
    )
    (net (code "89") (name "Net-(X4-LED1+)") (class "Default")
      (node (ref "R41") (pin "1") (pinfunction "1_1") (pintype "passive"))
      (node (ref "X4") (pin "13") (pinfunction "LED1+_13") (pintype "passive"))
    )
    (net (code "90") (name "Net-(X4-LED1-)") (class "Default")
      (node (ref "R43") (pin "1") (pinfunction "1_1") (pintype "passive"))
      (node (ref "X4") (pin "14") (pinfunction "LED1-_14") (pintype "passive"))
    )
    (net (code "91") (name "Net-(X4-LED2+G)") (class "Default")
      (node (ref "R44") (pin "1") (pinfunction "1_1") (pintype "passive"))
      (node (ref "X4") (pin "11") (pinfunction "LED2+G_11") (pintype "passive"))
    )
    (net (code "92") (name "Net-(X4-LED2+Y)") (class "Default")
      (node (ref "R42") (pin "1") (pinfunction "1_1") (pintype "passive"))
      (node (ref "X4") (pin "12") (pinfunction "LED2+Y_12") (pintype "passive"))
    )
    (net (code "93") (name "Net-(X4-VCC)") (class "Default")
      (node (ref "C32") (pin "2") (pinfunction "2_2") (pintype "passive"))
      (node (ref "L4") (pin "2") (pinfunction "2_2") (pintype "passive"))
      (node (ref "X4") (pin "2") (pinfunction "VCC_2") (pintype "passive"))
    )
    (net (code "94") (name "unconnected-(U9C-LPED_EN_N{slash}TDI-Pad14)") (class "Default")
      (node (ref "U9") (pin "14") (pinfunction "LPED_EN_N/TDI_14") (pintype "passive+no_connect"))
    )
    (net (code "95") (name "unconnected-(U9C-PHYAD1{slash}LED100-Pad43)") (class "Default")
      (node (ref "U9") (pin "43") (pinfunction "PHYAD1/LED100_43") (pintype "passive+no_connect"))
    )
    (net (code "96") (name "unconnected-(U9C-PHYAD2-Pad42)") (class "Default")
      (node (ref "U9") (pin "42") (pinfunction "PHYAD2_42") (pintype "passive+no_connect"))
    )
    (net (code "97") (name "unconnected-(U9C-PHYAD3-Pad41)") (class "Default")
      (node (ref "U9") (pin "41") (pinfunction "PHYAD3_41") (pintype "passive+no_connect"))
    )
    (net (code "98") (name "unconnected-(U9C-PHYAD4-Pad40)") (class "Default")
      (node (ref "U9") (pin "40") (pinfunction "PHYAD4_40") (pintype "passive+no_connect"))
    )
    (net (code "99") (name "unconnected-(U9D-TCK-Pad5)") (class "Default")
      (node (ref "U9") (pin "5") (pinfunction "TCK_5") (pintype "passive+no_connect"))
    )
    (net (code "100") (name "unconnected-(U9D-TDO-Pad15)") (class "Default")
      (node (ref "U9") (pin "15") (pinfunction "TDO_15") (pintype "passive+no_connect"))
    )
    (net (code "101") (name "unconnected-(U9D-XTAL_2-Pad23)") (class "Default")
      (node (ref "U9") (pin "23") (pinfunction "XTAL_2_23") (pintype "passive+no_connect"))
    )
    (net (code "102") (name "unconnected-(U9D-~{TRST}-Pad12)") (class "Default")
      (node (ref "U9") (pin "12") (pinfunction "~{TRST}_12") (pintype "passive+no_connect"))
    )
  )
)
